# electronic_stopwatch.net
KiCad netlist of a schematic drawn in Altium Designer
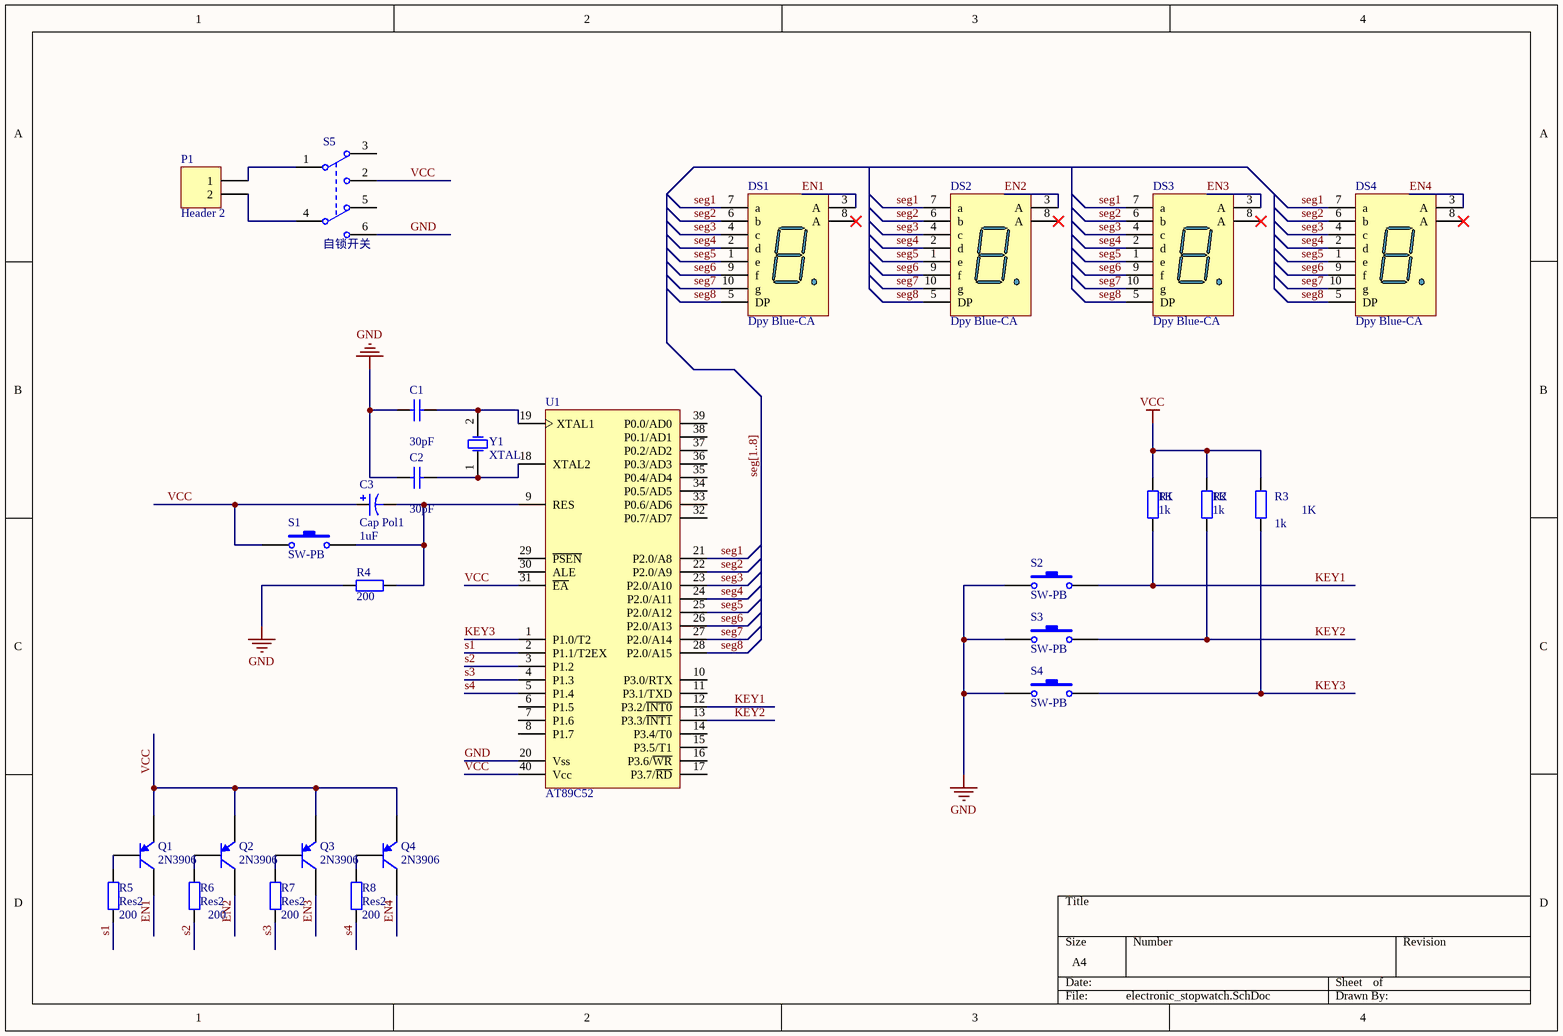
[diagram p0: electronic_stopwatch.SchDoc]

(export (version "E")
  (design (tool "Eeschema 10.0.6"))
  (components
    (comp (ref "C1")
      (value "30pF")
      (footprint "MLCC5.08-A")
      (description "Capacitor")
      (fields (field (name "Comment") "Cap") (field (name "PUBLISHER") "Altium Limited"))
      (libsource (lib "Miscellaneous Devices") (part "Cap"))
    )
    (comp (ref "C2")
      (value "30pF")
      (footprint "MLCC5.08-A")
      (description "Capacitor")
      (fields (field (name "Comment") "Cap") (field (name "PUBLISHER") "Altium Limited"))
      (libsource (lib "Miscellaneous Devices") (part "Cap"))
    )
    (comp (ref "C3")
      (value "Cap Pol1")
      (footprint "CAP 1.5*4*8")
      (description "Polarized Capacitor (Radial)")
      (fields (field (name "ALTIUM_VALUE") "1uF") (field (name "PUBLISHER") "Altium Limited"))
      (libsource (lib "Miscellaneous Devices") (part "Cap Pol1"))
    )
    (comp (ref "DS1")
      (value "Dpy Blue-CA")
      (footprint "SEG1_1_5611")
      (description "14.2 mm General Purpose Blue 7-Segment Display: CA, RH DP, Gray Surface")
      (fields (field (name "PUBLISHER") "Altium Limited"))
      (libsource (lib "Miscellaneous Devices") (part "Dpy Blue-CA"))
    )
    (comp (ref "DS2")
      (value "Dpy Blue-CA")
      (footprint "SEG1_1_5611")
      (description "14.2 mm General Purpose Blue 7-Segment Display: CA, RH DP, Gray Surface")
      (fields (field (name "PUBLISHER") "Altium Limited"))
      (libsource (lib "Miscellaneous Devices") (part "Dpy Blue-CA"))
    )
    (comp (ref "DS3")
      (value "Dpy Blue-CA")
      (footprint "SEG1_1_5611")
      (description "14.2 mm General Purpose Blue 7-Segment Display: CA, RH DP, Gray Surface")
      (fields (field (name "PUBLISHER") "Altium Limited"))
      (libsource (lib "Miscellaneous Devices") (part "Dpy Blue-CA"))
    )
    (comp (ref "DS4")
      (value "Dpy Blue-CA")
      (footprint "SEG1_1_5611")
      (description "14.2 mm General Purpose Blue 7-Segment Display: CA, RH DP, Gray Surface")
      (fields (field (name "PUBLISHER") "Altium Limited"))
      (libsource (lib "Miscellaneous Devices") (part "Dpy Blue-CA"))
    )
    (comp (ref "P1")
      (value "Header 2")
      (footprint "XH2.54-2P")
      (description "Header, 2-Pin")
      (fields (field (name "PUBLISHER") "Altium Limited"))
      (libsource (lib "Miscellaneous Connectors") (part "Header 2"))
    )
    (comp (ref "Q1")
      (value "2N3906")
      (footprint "to-92")
      (description "PNP General Purpose Amplifier")
      (fields (field (name "PUBLISHER") "Altium Limited"))
      (libsource (lib "Miscellaneous Devices") (part "2N3906"))
    )
    (comp (ref "Q2")
      (value "2N3906")
      (footprint "to-92")
      (description "PNP General Purpose Amplifier")
      (fields (field (name "PUBLISHER") "Altium Limited"))
      (libsource (lib "Miscellaneous Devices") (part "2N3906"))
    )
    (comp (ref "Q3")
      (value "2N3906")
      (footprint "to-92")
      (description "PNP General Purpose Amplifier")
      (fields (field (name "PUBLISHER") "Altium Limited"))
      (libsource (lib "Miscellaneous Devices") (part "2N3906"))
    )
    (comp (ref "Q4")
      (value "2N3906")
      (footprint "to-92")
      (description "PNP General Purpose Amplifier")
      (fields (field (name "PUBLISHER") "Altium Limited"))
      (libsource (lib "Miscellaneous Devices") (part "2N3906"))
    )
    (comp (ref "R1")
      (value "1K")
      (footprint "RS 1/4W")
      (description "Resistor")
      (fields (field (name "ALTIUM_VALUE") "1k") (field (name "PUBLISHER") "Altium Limited"))
      (libsource (lib "altium-import") (part "root_3__Miscellaneous Devices.IntLib"))
    )
    (comp (ref "R2")
      (value "1K")
      (footprint "RS 1/4W")
      (description "Resistor")
      (fields (field (name "ALTIUM_VALUE") "1k") (field (name "PUBLISHER") "Altium Limited"))
      (libsource (lib "altium-import") (part "root_3__Miscellaneous Devices.IntLib"))
    )
    (comp (ref "R3")
      (value "1K")
      (footprint "RS 1/4W")
      (description "Resistor")
      (fields (field (name "ALTIUM_VALUE") "1k") (field (name "PUBLISHER") "Altium Limited"))
      (libsource (lib "altium-import") (part "root_3__Miscellaneous Devices.IntLib"))
    )
    (comp (ref "R4")
      (value "200")
      (footprint "RS 1/4W")
      (description "Resistor")
      (fields (field (name "PUBLISHER") "Altium Limited"))
      (libsource (lib "altium-import") (part "root_0__Miscellaneous Devices.IntLib"))
    )
    (comp (ref "R5")
      (value "Res2")
      (footprint "RS 1/4W")
      (description "Resistor")
      (fields (field (name "ALTIUM_VALUE") "200") (field (name "PUBLISHER") "Altium Limited"))
      (libsource (lib "Miscellaneous Devices") (part "Res2"))
    )
    (comp (ref "R6")
      (value "Res2")
      (footprint "RS 1/4W")
      (description "Resistor")
      (fields (field (name "ALTIUM_VALUE") "200") (field (name "PUBLISHER") "Altium Limited"))
      (libsource (lib "Miscellaneous Devices") (part "Res2"))
    )
    (comp (ref "R7")
      (value "Res2")
      (footprint "RS 1/4W")
      (description "Resistor")
      (fields (field (name "ALTIUM_VALUE") "200") (field (name "PUBLISHER") "Altium Limited"))
      (libsource (lib "Miscellaneous Devices") (part "Res2"))
    )
    (comp (ref "R8")
      (value "Res2")
      (footprint "RS 1/4W")
      (description "Resistor")
      (fields (field (name "ALTIUM_VALUE") "200") (field (name "PUBLISHER") "Altium Limited"))
      (libsource (lib "Miscellaneous Devices") (part "Res2"))
    )
    (comp (ref "S1")
      (value "SW-PB")
      (footprint "TSW DIP-6*6*6")
      (description "Switch")
      (fields (field (name "PUBLISHER") "Altium Limited"))
      (libsource (lib "Miscellaneous Devices") (part "SW-PB"))
    )
    (comp (ref "S2")
      (value "SW-PB")
      (footprint "TSW DIP-6*6*6")
      (description "Switch")
      (fields (field (name "PUBLISHER") "Altium Limited"))
      (libsource (lib "Miscellaneous Devices") (part "SW-PB"))
    )
    (comp (ref "S3")
      (value "SW-PB")
      (footprint "TSW DIP-6*6*6")
      (description "Switch")
      (fields (field (name "PUBLISHER") "Altium Limited"))
      (libsource (lib "Miscellaneous Devices") (part "SW-PB"))
    )
    (comp (ref "S4")
      (value "SW-PB")
      (footprint "TSW DIP-6*6*6")
      (description "Switch")
      (fields (field (name "PUBLISHER") "Altium Limited"))
      (libsource (lib "Miscellaneous Devices") (part "SW-PB"))
    )
    (comp (ref "S5")
      (value "自锁开关")
      (footprint "sw_8.5mm")
      (libsource (lib "02-Miscellaneous_Devices_ZSF_Library") (part "SW DPDT"))
    )
    (comp (ref "U1") (value "AT89C52") (footprint "DIP40-600_MH带底座") (libsource (lib "*") (part "AT89C52")))
    (comp (ref "Y1")
      (value "XTAL")
      (footprint "cry卧式")
      (description "Crystal Oscillator")
      (fields (field (name "PUBLISHER") "Altium Limited"))
      (libsource (lib "Miscellaneous Devices") (part "XTAL"))
    )
  )
  (nets
    (net (code "1") (name "/EN1") (class "Default")
      (node (ref "DS1") (pin "3") (pinfunction "A_3") (pintype "passive"))
      (node (ref "Q1") (pin "3") (pinfunction "C_3") (pintype "passive"))
    )
    (net (code "2") (name "/EN2") (class "Default")
      (node (ref "DS2") (pin "3") (pinfunction "A_3") (pintype "passive"))
      (node (ref "Q2") (pin "3") (pinfunction "C_3") (pintype "passive"))
    )
    (net (code "3") (name "/EN3") (class "Default")
      (node (ref "DS3") (pin "3") (pinfunction "A_3") (pintype "passive"))
      (node (ref "Q3") (pin "3") (pinfunction "C_3") (pintype "passive"))
    )
    (net (code "4") (name "/EN4") (class "Default")
      (node (ref "DS4") (pin "3") (pinfunction "A_3") (pintype "passive"))
      (node (ref "Q4") (pin "3") (pinfunction "C_3") (pintype "passive"))
    )
    (net (code "5") (name "/KEY1") (class "Default")
      (node (ref "R1") (pin "2") (pinfunction "2_2") (pintype "passive"))
      (node (ref "S2") (pin "2") (pinfunction "2_2") (pintype "passive"))
      (node (ref "U1") (pin "12") (pinfunction "P3.2/~{INT0}_12") (pintype "passive"))
    )
    (net (code "6") (name "/KEY2") (class "Default")
      (node (ref "R2") (pin "2") (pinfunction "2_2") (pintype "passive"))
      (node (ref "S3") (pin "2") (pinfunction "2_2") (pintype "passive"))
      (node (ref "U1") (pin "13") (pinfunction "P3.3/~{INT1}_13") (pintype "passive"))
    )
    (net (code "7") (name "/KEY3") (class "Default")
      (node (ref "R3") (pin "2") (pinfunction "2_2") (pintype "passive"))
      (node (ref "S4") (pin "2") (pinfunction "2_2") (pintype "passive"))
      (node (ref "U1") (pin "1") (pinfunction "P1.0/T2_1") (pintype "passive"))
    )
    (net (code "8") (name "/s1") (class "Default")
      (node (ref "R5") (pin "1") (pinfunction "1_1") (pintype "passive"))
      (node (ref "U1") (pin "2") (pinfunction "P1.1/T2EX_2") (pintype "passive"))
    )
    (net (code "9") (name "/s2") (class "Default")
      (node (ref "R6") (pin "1") (pinfunction "1_1") (pintype "passive"))
      (node (ref "U1") (pin "3") (pinfunction "P1.2_3") (pintype "passive"))
    )
    (net (code "10") (name "/s3") (class "Default")
      (node (ref "R7") (pin "1") (pinfunction "1_1") (pintype "passive"))
      (node (ref "U1") (pin "4") (pinfunction "P1.3_4") (pintype "passive"))
    )
    (net (code "11") (name "/s4") (class "Default")
      (node (ref "R8") (pin "1") (pinfunction "1_1") (pintype "passive"))
      (node (ref "U1") (pin "5") (pinfunction "P1.4_5") (pintype "passive"))
    )
    (net (code "12") (name "/seg1") (class "Default")
      (node (ref "DS1") (pin "7") (pinfunction "a_7") (pintype "passive"))
      (node (ref "DS2") (pin "7") (pinfunction "a_7") (pintype "passive"))
      (node (ref "DS3") (pin "7") (pinfunction "a_7") (pintype "passive"))
      (node (ref "DS4") (pin "7") (pinfunction "a_7") (pintype "passive"))
      (node (ref "U1") (pin "21") (pinfunction "P2.0/A8_21") (pintype "passive"))
    )
    (net (code "13") (name "/seg2") (class "Default")
      (node (ref "DS1") (pin "6") (pinfunction "b_6") (pintype "passive"))
      (node (ref "DS2") (pin "6") (pinfunction "b_6") (pintype "passive"))
      (node (ref "DS3") (pin "6") (pinfunction "b_6") (pintype "passive"))
      (node (ref "DS4") (pin "6") (pinfunction "b_6") (pintype "passive"))
      (node (ref "U1") (pin "22") (pinfunction "P2.0/A9_22") (pintype "passive"))
    )
    (net (code "14") (name "/seg3") (class "Default")
      (node (ref "DS1") (pin "4") (pinfunction "c_4") (pintype "passive"))
      (node (ref "DS2") (pin "4") (pinfunction "c_4") (pintype "passive"))
      (node (ref "DS3") (pin "4") (pinfunction "c_4") (pintype "passive"))
      (node (ref "DS4") (pin "4") (pinfunction "c_4") (pintype "passive"))
      (node (ref "U1") (pin "23") (pinfunction "P2.0/A10_23") (pintype "passive"))
    )
    (net (code "15") (name "/seg4") (class "Default")
      (node (ref "DS1") (pin "2") (pinfunction "d_2") (pintype "passive"))
      (node (ref "DS2") (pin "2") (pinfunction "d_2") (pintype "passive"))
      (node (ref "DS3") (pin "2") (pinfunction "d_2") (pintype "passive"))
      (node (ref "DS4") (pin "2") (pinfunction "d_2") (pintype "passive"))
      (node (ref "U1") (pin "24") (pinfunction "P2.0/A11_24") (pintype "passive"))
    )
    (net (code "16") (name "/seg5") (class "Default")
      (node (ref "DS1") (pin "1") (pinfunction "e_1") (pintype "passive"))
      (node (ref "DS2") (pin "1") (pinfunction "e_1") (pintype "passive"))
      (node (ref "DS3") (pin "1") (pinfunction "e_1") (pintype "passive"))
      (node (ref "DS4") (pin "1") (pinfunction "e_1") (pintype "passive"))
      (node (ref "U1") (pin "25") (pinfunction "P2.0/A12_25") (pintype "passive"))
    )
    (net (code "17") (name "/seg6") (class "Default")
      (node (ref "DS1") (pin "9") (pinfunction "f_9") (pintype "passive"))
      (node (ref "DS2") (pin "9") (pinfunction "f_9") (pintype "passive"))
      (node (ref "DS3") (pin "9") (pinfunction "f_9") (pintype "passive"))
      (node (ref "DS4") (pin "9") (pinfunction "f_9") (pintype "passive"))
      (node (ref "U1") (pin "26") (pinfunction "P2.0/A13_26") (pintype "passive"))
    )
    (net (code "18") (name "/seg7") (class "Default")
      (node (ref "DS1") (pin "10") (pinfunction "g_10") (pintype "passive"))
      (node (ref "DS2") (pin "10") (pinfunction "g_10") (pintype "passive"))
      (node (ref "DS3") (pin "10") (pinfunction "g_10") (pintype "passive"))
      (node (ref "DS4") (pin "10") (pinfunction "g_10") (pintype "passive"))
      (node (ref "U1") (pin "27") (pinfunction "P2.0/A14_27") (pintype "passive"))
    )
    (net (code "19") (name "/seg8") (class "Default")
      (node (ref "DS1") (pin "5") (pinfunction "DP_5") (pintype "passive"))
      (node (ref "DS2") (pin "5") (pinfunction "DP_5") (pintype "passive"))
      (node (ref "DS3") (pin "5") (pinfunction "DP_5") (pintype "passive"))
      (node (ref "DS4") (pin "5") (pinfunction "DP_5") (pintype "passive"))
      (node (ref "U1") (pin "28") (pinfunction "P2.0/A15_28") (pintype "passive"))
    )
    (net (code "21") (name "GND") (class "Default")
      (node (ref "C1") (pin "1") (pinfunction "1_1") (pintype "passive"))
      (node (ref "C2") (pin "1") (pinfunction "1_1") (pintype "passive"))
      (node (ref "R4") (pin "1") (pinfunction "1_1") (pintype "passive"))
      (node (ref "S2") (pin "1") (pinfunction "1_1") (pintype "passive"))
      (node (ref "S3") (pin "1") (pinfunction "1_1") (pintype "passive"))
      (node (ref "S4") (pin "1") (pinfunction "1_1") (pintype "passive"))
      (node (ref "S5") (pin "6") (pinfunction "6_6") (pintype "passive"))
      (node (ref "U1") (pin "20") (pinfunction "Vss_20") (pintype "passive"))
    )
    (net (code "22") (name "Net-(P1-Pad1)") (class "Default")
      (node (ref "P1") (pin "1") (pinfunction "1_1") (pintype "passive"))
      (node (ref "S5") (pin "1") (pinfunction "1_1") (pintype "passive"))
    )
    (net (code "23") (name "Net-(P1-Pad2)") (class "Default")
      (node (ref "P1") (pin "2") (pinfunction "2_2") (pintype "passive"))
      (node (ref "S5") (pin "4") (pinfunction "4_4") (pintype "passive"))
    )
    (net (code "24") (name "Net-(Q1-B)") (class "Default")
      (node (ref "Q1") (pin "2") (pinfunction "B_2") (pintype "passive"))
      (node (ref "R5") (pin "2") (pinfunction "2_2") (pintype "passive"))
    )
    (net (code "25") (name "Net-(Q2-B)") (class "Default")
      (node (ref "Q2") (pin "2") (pinfunction "B_2") (pintype "passive"))
      (node (ref "R6") (pin "2") (pinfunction "2_2") (pintype "passive"))
    )
    (net (code "26") (name "Net-(Q3-B)") (class "Default")
      (node (ref "Q3") (pin "2") (pinfunction "B_2") (pintype "passive"))
      (node (ref "R7") (pin "2") (pinfunction "2_2") (pintype "passive"))
    )
    (net (code "27") (name "Net-(Q4-B)") (class "Default")
      (node (ref "Q4") (pin "2") (pinfunction "B_2") (pintype "passive"))
      (node (ref "R8") (pin "2") (pinfunction "2_2") (pintype "passive"))
    )
    (net (code "28") (name "Net-(U1-RES)") (class "Default")
      (node (ref "C3") (pin "2") (pinfunction "2_2") (pintype "passive"))
      (node (ref "R4") (pin "2") (pinfunction "2_2") (pintype "passive"))
      (node (ref "S1") (pin "2") (pinfunction "2_2") (pintype "passive"))
      (node (ref "U1") (pin "9") (pinfunction "RES_9") (pintype "passive"))
    )
    (net (code "29") (name "Net-(U1-XTAL1)") (class "Default")
      (node (ref "C1") (pin "2") (pinfunction "2_2") (pintype "passive"))
      (node (ref "U1") (pin "19") (pinfunction "XTAL1_19") (pintype "passive"))
      (node (ref "Y1") (pin "2") (pinfunction "OSC2_2") (pintype "passive"))
    )
    (net (code "30") (name "Net-(U1-XTAL2)") (class "Default")
      (node (ref "C2") (pin "2") (pinfunction "2_2") (pintype "passive"))
      (node (ref "U1") (pin "18") (pinfunction "XTAL2_18") (pintype "passive"))
      (node (ref "Y1") (pin "1") (pinfunction "OSC1_1") (pintype "passive"))
    )
    (net (code "31") (name "VCC") (class "Default")
      (node (ref "C3") (pin "1") (pinfunction "1_1") (pintype "passive"))
      (node (ref "Q1") (pin "1") (pinfunction "E_1") (pintype "passive"))
      (node (ref "Q2") (pin "1") (pinfunction "E_1") (pintype "passive"))
      (node (ref "Q3") (pin "1") (pinfunction "E_1") (pintype "passive"))
      (node (ref "Q4") (pin "1") (pinfunction "E_1") (pintype "passive"))
      (node (ref "R1") (pin "1") (pinfunction "1_1") (pintype "passive"))
      (node (ref "R2") (pin "1") (pinfunction "1_1") (pintype "passive"))
      (node (ref "R3") (pin "1") (pinfunction "1_1") (pintype "passive"))
      (node (ref "S1") (pin "1") (pinfunction "1_1") (pintype "passive"))
      (node (ref "S5") (pin "2") (pinfunction "2_2") (pintype "passive"))
      (node (ref "U1") (pin "31") (pinfunction "~{EA}_31") (pintype "passive"))
      (node (ref "U1") (pin "40") (pinfunction "Vcc_40") (pintype "passive"))
    )
    (net (code "32") (name "unconnected-(DS1-A-Pad8)") (class "Default")
      (node (ref "DS1") (pin "8") (pinfunction "A_8") (pintype "passive+no_connect"))
    )
    (net (code "33") (name "unconnected-(DS2-A-Pad8)") (class "Default")
      (node (ref "DS2") (pin "8") (pinfunction "A_8") (pintype "passive+no_connect"))
    )
    (net (code "34") (name "unconnected-(DS3-A-Pad8)") (class "Default")
      (node (ref "DS3") (pin "8") (pinfunction "A_8") (pintype "passive+no_connect"))
    )
    (net (code "35") (name "unconnected-(DS4-A-Pad8)") (class "Default")
      (node (ref "DS4") (pin "8") (pinfunction "A_8") (pintype "passive+no_connect"))
    )
    (net (code "36") (name "unconnected-(S5-Pad3)") (class "Default")
      (node (ref "S5") (pin "3") (pinfunction "3_3") (pintype "passive"))
    )
    (net (code "37") (name "unconnected-(S5-Pad5)") (class "Default")
      (node (ref "S5") (pin "5") (pinfunction "5_5") (pintype "passive"))
    )
    (net (code "38") (name "unconnected-(U1-ALE-Pad30)") (class "Default")
      (node (ref "U1") (pin "30") (pinfunction "ALE_30") (pintype "passive"))
    )
    (net (code "39") (name "unconnected-(U1-P0.0{slash}AD0-Pad39)") (class "Default")
      (node (ref "U1") (pin "39") (pinfunction "P0.0/AD0_39") (pintype "passive"))
    )
    (net (code "40") (name "unconnected-(U1-P0.1{slash}AD1-Pad38)") (class "Default")
      (node (ref "U1") (pin "38") (pinfunction "P0.1/AD1_38") (pintype "passive"))
    )
    (net (code "41") (name "unconnected-(U1-P0.2{slash}AD2-Pad37)") (class "Default")
      (node (ref "U1") (pin "37") (pinfunction "P0.2/AD2_37") (pintype "passive"))
    )
    (net (code "42") (name "unconnected-(U1-P0.3{slash}AD3-Pad36)") (class "Default")
      (node (ref "U1") (pin "36") (pinfunction "P0.3/AD3_36") (pintype "passive"))
    )
    (net (code "43") (name "unconnected-(U1-P0.4{slash}AD4-Pad35)") (class "Default")
      (node (ref "U1") (pin "35") (pinfunction "P0.4/AD4_35") (pintype "passive"))
    )
    (net (code "44") (name "unconnected-(U1-P0.5{slash}AD5-Pad34)") (class "Default")
      (node (ref "U1") (pin "34") (pinfunction "P0.5/AD5_34") (pintype "passive"))
    )
    (net (code "45") (name "unconnected-(U1-P0.6{slash}AD6-Pad33)") (class "Default")
      (node (ref "U1") (pin "33") (pinfunction "P0.6/AD6_33") (pintype "passive"))
    )
    (net (code "46") (name "unconnected-(U1-P0.7{slash}AD7-Pad32)") (class "Default")
      (node (ref "U1") (pin "32") (pinfunction "P0.7/AD7_32") (pintype "passive"))
    )
    (net (code "47") (name "unconnected-(U1-P1.5-Pad6)") (class "Default")
      (node (ref "U1") (pin "6") (pinfunction "P1.5_6") (pintype "passive"))
    )
    (net (code "48") (name "unconnected-(U1-P1.6-Pad7)") (class "Default")
      (node (ref "U1") (pin "7") (pinfunction "P1.6_7") (pintype "passive"))
    )
    (net (code "49") (name "unconnected-(U1-P1.7-Pad8)") (class "Default")
      (node (ref "U1") (pin "8") (pinfunction "P1.7_8") (pintype "passive"))
    )
    (net (code "50") (name "unconnected-(U1-P3.0{slash}RTX-Pad10)") (class "Default")
      (node (ref "U1") (pin "10") (pinfunction "P3.0/RTX_10") (pintype "passive"))
    )
    (net (code "51") (name "unconnected-(U1-P3.1{slash}TXD-Pad11)") (class "Default")
      (node (ref "U1") (pin "11") (pinfunction "P3.1/TXD_11") (pintype "passive"))
    )
    (net (code "52") (name "unconnected-(U1-P3.4{slash}T0-Pad14)") (class "Default")
      (node (ref "U1") (pin "14") (pinfunction "P3.4/T0_14") (pintype "passive"))
    )
    (net (code "53") (name "unconnected-(U1-P3.5{slash}T1-Pad15)") (class "Default")
      (node (ref "U1") (pin "15") (pinfunction "P3.5/T1_15") (pintype "passive"))
    )
    (net (code "54") (name "unconnected-(U1-P3.6{slash}~{WR}-Pad16)") (class "Default")
      (node (ref "U1") (pin "16") (pinfunction "P3.6/~{WR}_16") (pintype "passive"))
    )
    (net (code "55") (name "unconnected-(U1-P3.7{slash}~{RD}-Pad17)") (class "Default")
      (node (ref "U1") (pin "17") (pinfunction "P3.7/~{RD}_17") (pintype "passive"))
    )
    (net (code "56") (name "unconnected-(U1-~{PSEN}-Pad29)") (class "Default")
      (node (ref "U1") (pin "29") (pinfunction "~{PSEN}_29") (pintype "passive"))
    )
  )
)
